# power.net
KiCad netlist of a schematic drawn in Altium Designer
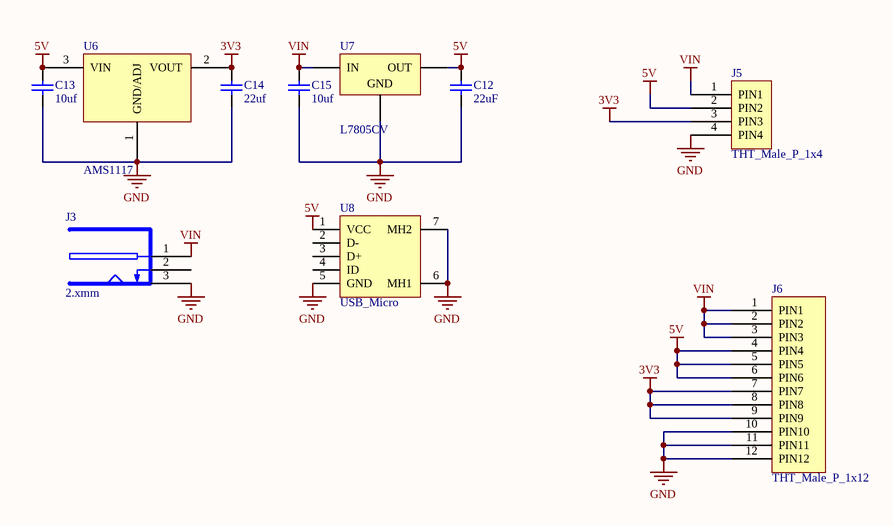
[diagram p0: power.SchDoc]

(export (version "E")
  (design (tool "Eeschema 10.0.6"))
  (components
    (comp (ref "C12")
      (value "22uF")
      (footprint "1210")
      (description "Capacitor")
      (libsource (lib "MySch") (part "CAP"))
    )
    (comp (ref "C13")
      (value "10uf")
      (footprint "1210")
      (description "Ceramic Chip Capacitor - Standard")
      (fields (field (name "Comment") "Capacitor") (field (name "PUBLISHER") "Altium Limited"))
      (libsource (lib "MySch") (part "Capacitor"))
    )
    (comp (ref "C14")
      (value "22uf")
      (footprint "1210")
      (description "Ceramic Chip Capacitor - Standard")
      (fields (field (name "Comment") "Capacitor") (field (name "PUBLISHER") "Altium Limited"))
      (libsource (lib "MySch") (part "Capacitor"))
    )
    (comp (ref "C15")
      (value "10uf")
      (footprint "1210")
      (description "Capacitor")
      (libsource (lib "MySch") (part "CAP"))
    )
    (comp (ref "J3")
      (value "2.xmm")
      (footprint "FP_DC_TAP_ANYA")
      (description "2.xmm DC HEBA25 TÁPFESZÜLTSÉG ALJZAT ZÁRT, NYÁKBA 90°")
      (libsource (lib "MySch") (part "DC_TAP_ANYA"))
    )
    (comp (ref "J5")
      (value "THT_Male_P_1x4")
      (footprint "THT_Male_P_1x4-2.54mm")
      (description "THT Male pin header strip 1x4")
      (libsource (lib "Vowstar_Connector") (part "THT_Male_P_1x4"))
    )
    (comp (ref "J6")
      (value "THT_Male_P_1x12")
      (footprint "THT_Male_P_1x12-2.54mm")
      (description "THT Male pin header strip 1x12")
      (libsource (lib "Vowstar_Connector") (part "THT_Male_P_1x12"))
    )
    (comp (ref "U6")
      (value "AMS1117")
      (footprint "AMS1117-ADJ")
      (description "AMS1117 1A LOW DROPOUT VOLTAGE REGULATOR")
      (libsource (lib "Vowstar_IC_General") (part "AMS1117"))
    )
    (comp (ref "U7")
      (value "L7805CV")
      (footprint "SOT-223")
      (description "Positive Voltage Regulator")
      (fields (field (name "PUBLISHER") "Altium Limited"))
      (libsource (lib "MySch") (part "L7805CV"))
    )
    (comp (ref "U8")
      (value "USB_Micro")
      (footprint "USB_Micro_Standard")
      (description "USB micro female")
      (libsource (lib "Vowstar_Connector") (part "USB_Micro"))
    )
  )
  (nets
    (net (code "1") (name "3V3") (class "Default")
      (node (ref "C14") (pin "2") (pinfunction "2_2") (pintype "passive"))
      (node (ref "J5") (pin "3") (pinfunction "PIN3_3") (pintype "passive"))
      (node (ref "J6") (pin "7") (pinfunction "PIN7_7") (pintype "passive"))
      (node (ref "J6") (pin "8") (pinfunction "PIN8_8") (pintype "passive"))
      (node (ref "J6") (pin "9") (pinfunction "PIN9_9") (pintype "passive"))
      (node (ref "U6") (pin "2") (pinfunction "VOUT_2") (pintype "passive"))
    )
    (net (code "2") (name "5V") (class "Default")
      (node (ref "C12") (pin "2") (pinfunction "2_2") (pintype "passive"))
      (node (ref "C13") (pin "2") (pinfunction "2_2") (pintype "passive"))
      (node (ref "J5") (pin "2") (pinfunction "PIN2_2") (pintype "passive"))
      (node (ref "J6") (pin "4") (pinfunction "PIN4_4") (pintype "passive"))
      (node (ref "J6") (pin "5") (pinfunction "PIN5_5") (pintype "passive"))
      (node (ref "J6") (pin "6") (pinfunction "PIN6_6") (pintype "passive"))
      (node (ref "U6") (pin "3") (pinfunction "VIN_3") (pintype "passive"))
      (node (ref "U7") (pin "OUT") (pinfunction "OUT_OUT") (pintype "power_in"))
      (node (ref "U8") (pin "1") (pinfunction "VCC_1") (pintype "passive"))
    )
    (net (code "3") (name "GND") (class "Default")
      (node (ref "C12") (pin "1") (pinfunction "1_1") (pintype "passive"))
      (node (ref "C13") (pin "1") (pinfunction "1_1") (pintype "passive"))
      (node (ref "C14") (pin "1") (pinfunction "1_1") (pintype "passive"))
      (node (ref "C15") (pin "1") (pinfunction "1_1") (pintype "passive"))
      (node (ref "J3") (pin "3") (pinfunction "GND_3") (pintype "power_in"))
      (node (ref "J5") (pin "4") (pinfunction "PIN4_4") (pintype "passive"))
      (node (ref "J6") (pin "10") (pinfunction "PIN10_10") (pintype "passive"))
      (node (ref "J6") (pin "11") (pinfunction "PIN11_11") (pintype "passive"))
      (node (ref "J6") (pin "12") (pinfunction "PIN12_12") (pintype "passive"))
      (node (ref "U6") (pin "1") (pinfunction "GND/ADJ_1") (pintype "passive"))
      (node (ref "U7") (pin "GND") (pinfunction "GND_GND") (pintype "power_in"))
      (node (ref "U8") (pin "5") (pinfunction "GND_5") (pintype "passive"))
      (node (ref "U8") (pin "6") (pinfunction "MH1_6") (pintype "passive"))
      (node (ref "U8") (pin "7") (pinfunction "MH2_7") (pintype "passive"))
    )
    (net (code "4") (name "VIN") (class "Default")
      (node (ref "C15") (pin "2") (pinfunction "2_2") (pintype "passive"))
      (node (ref "J3") (pin "1") (pinfunction "9V_1") (pintype "power_in"))
      (node (ref "J5") (pin "1") (pinfunction "PIN1_1") (pintype "passive"))
      (node (ref "J6") (pin "1") (pinfunction "PIN1_1") (pintype "passive"))
      (node (ref "J6") (pin "2") (pinfunction "PIN2_2") (pintype "passive"))
      (node (ref "J6") (pin "3") (pinfunction "PIN3_3") (pintype "passive"))
      (node (ref "U7") (pin "IN") (pinfunction "IN_IN") (pintype "power_in"))
    )
    (net (code "5") (name "unconnected-(J3-GND-Pad2)") (class "Default")
      (node (ref "J3") (pin "2") (pinfunction "GND_2") (pintype "power_in"))
    )
    (net (code "6") (name "unconnected-(U8-D+-Pad3)") (class "Default")
      (node (ref "U8") (pin "3") (pinfunction "D+_3") (pintype "passive"))
    )
    (net (code "7") (name "unconnected-(U8-D--Pad2)") (class "Default")
      (node (ref "U8") (pin "2") (pinfunction "D-_2") (pintype "passive"))
    )
    (net (code "8") (name "unconnected-(U8-ID-Pad4)") (class "Default")
      (node (ref "U8") (pin "4") (pinfunction "ID_4") (pintype "passive"))
    )
  )
)
